# PayloadBay.net
KiCad netlist of a schematic drawn in EAGLE
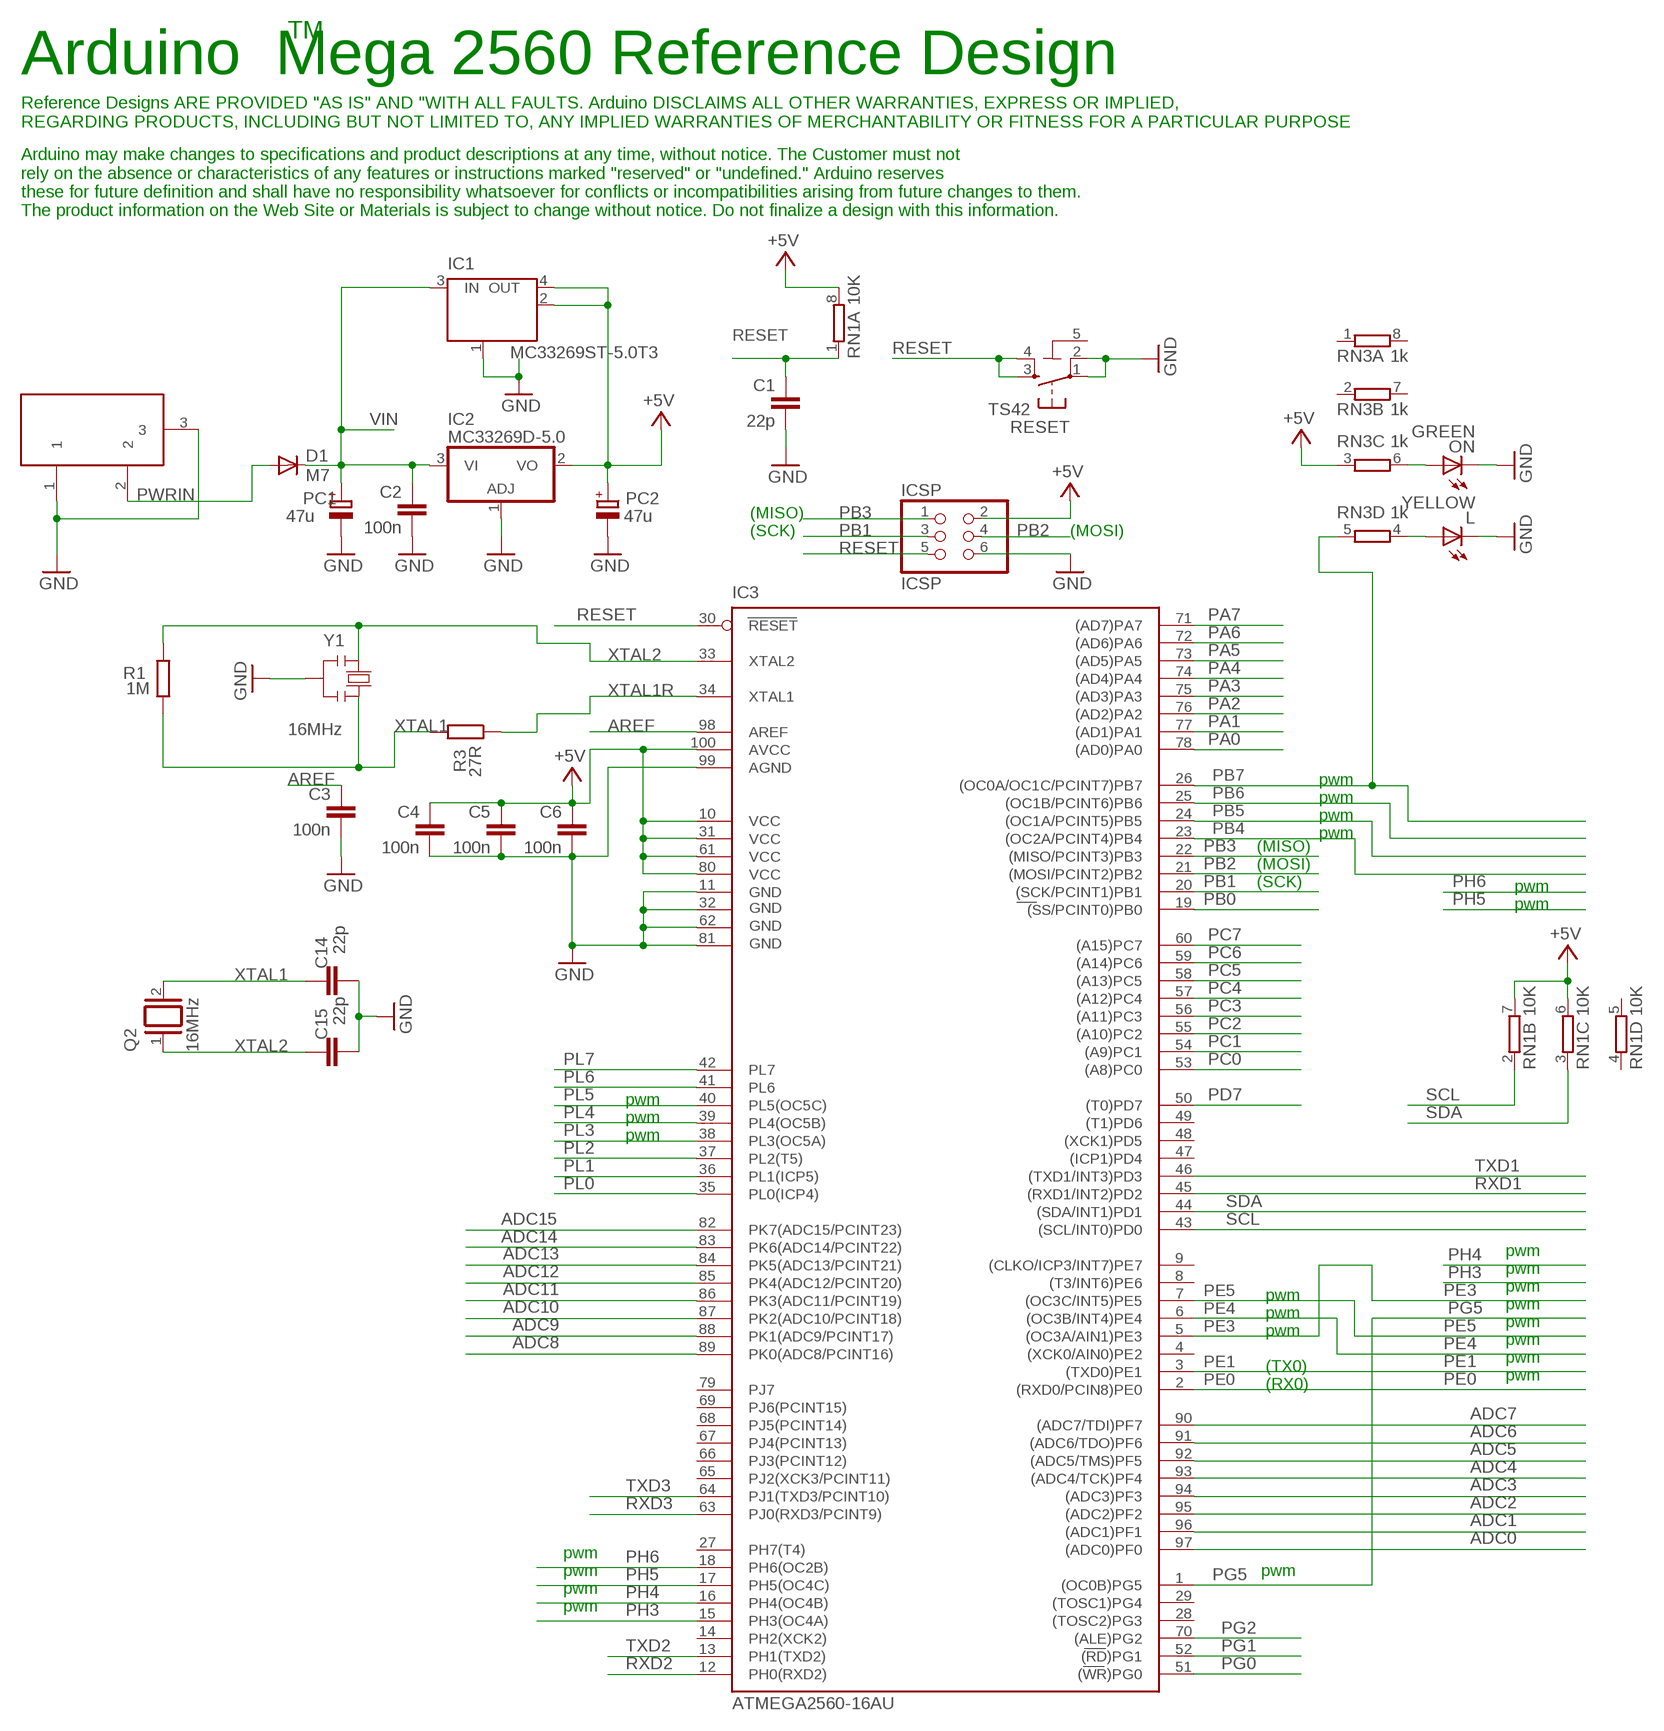
[diagram p0: schematic, sheet 1]

(export (version "E")
  (design (tool "Eeschema 10.0.6"))
  (components
    (comp (ref "C1")
      (value "22p")
      (footprint "eagle-import:C0603-ROUND")
      (libsource (lib "eagle-import") (part "C-EU0603-RND"))
    )
    (comp (ref "C2")
      (value "100n")
      (footprint "eagle-import:C0603-ROUND")
      (libsource (lib "eagle-import") (part "C-EU0603-RND"))
    )
    (comp (ref "C3")
      (value "100n")
      (footprint "eagle-import:C0603-ROUND")
      (libsource (lib "eagle-import") (part "C-EU0603-RND"))
    )
    (comp (ref "C4")
      (value "100n")
      (footprint "eagle-import:C0603-ROUND")
      (libsource (lib "eagle-import") (part "C-EU0603-RND"))
    )
    (comp (ref "C5")
      (value "100n")
      (footprint "eagle-import:C0603-ROUND")
      (libsource (lib "eagle-import") (part "C-EU0603-RND"))
    )
    (comp (ref "C6")
      (value "100n")
      (footprint "eagle-import:C0603-ROUND")
      (libsource (lib "eagle-import") (part "C-EU0603-RND"))
    )
    (comp (ref "C14")
      (value "22p")
      (footprint "eagle-import:C0603-ROUND")
      (libsource (lib "eagle-import") (part "C-EU0603-RND"))
    )
    (comp (ref "C15")
      (value "22p")
      (footprint "eagle-import:C0603-ROUND")
      (libsource (lib "eagle-import") (part "C-EU0603-RND"))
    )
    (comp (ref "D1")
      (value "M7")
      (footprint "eagle-import:SMB")
      (libsource (lib "eagle-import") (part "DIODE-SMB"))
    )
    (comp (ref "IC1")
      (value "MC33269ST-5.0T3")
      (footprint "eagle-import:SOT223")
      (libsource (lib "eagle-import") (part "MC33269ST-3.3T3"))
    )
    (comp (ref "IC2")
      (value "MC33269D-5.0")
      (footprint "eagle-import:DPACK")
      (libsource (lib "eagle-import") (part "MC33269?D-5.0"))
    )
    (comp (ref "IC3")
      (value "ATMEGA2560-16AU")
      (footprint "eagle-import:TQFP100")
      (libsource (lib "eagle-import") (part "ATMEGAAU1280-16"))
    )
    (comp (ref "ICSP")
      (value "ICSP")
      (footprint "eagle-import:2X03")
      (libsource (lib "eagle-import") (part "PINHD-2X3"))
    )
    (comp (ref "L")
      (value "YELLOW")
      (footprint "eagle-import:CHIP-LED0805")
      (libsource (lib "eagle-import") (part "LEDCHIP-LED0805"))
    )
    (comp (ref "ON")
      (value "GREEN")
      (footprint "eagle-import:CHIP-LED0805")
      (libsource (lib "eagle-import") (part "LEDCHIP-LED0805"))
    )
    (comp (ref "PC1")
      (value "47u")
      (footprint "eagle-import:PANASONIC_D")
      (libsource (lib "eagle-import") (part "CPOL-EUD"))
    )
    (comp (ref "PC2")
      (value "47u")
      (footprint "eagle-import:PANASONIC_D")
      (libsource (lib "eagle-import") (part "CPOL-EUD"))
    )
    (comp (ref "Q2")
      (value "16MHz")
      (footprint "eagle-import:QS")
      (libsource (lib "eagle-import") (part "XTAL/S"))
    )
    (comp (ref "R1")
      (value "1M")
      (footprint "eagle-import:R0603-ROUND")
      (libsource (lib "eagle-import") (part "R-EU_R0603"))
    )
    (comp (ref "R3")
      (value "27R")
      (footprint "eagle-import:R0603-ROUND")
      (libsource (lib "eagle-import") (part "R-EU_R0603"))
    )
    (comp (ref "RESET")
      (value "TS42")
      (footprint "eagle-import:TS42")
      (libsource (lib "eagle-import") (part "TS42"))
    )
    (comp (ref "RN1")
      (value "10K")
      (footprint "eagle-import:CAT16")
      (libsource (lib "eagle-import") (part "4R-NCAT16"))
    )
    (comp (ref "RN3")
      (value "1k")
      (footprint "eagle-import:CAY16")
      (libsource (lib "eagle-import") (part "4R-NCAY16"))
    )
    (comp (ref "X1")
      (value "DC21MMX")
      (footprint "eagle-import:DC-21MM")
      (libsource (lib "eagle-import") (part "DC21MMX"))
    )
    (comp (ref "Y1")
      (value "16MHz")
      (footprint "eagle-import:RESONATOR")
      (libsource (lib "eagle-import") (part "RESONATORMU"))
    )
  )
  (nets
    (net (code "1") (name "+5V") (class "Default")
      (node (ref "C4") (pin "1") (pinfunction "1_1") (pintype "passive"))
      (node (ref "C5") (pin "1") (pinfunction "1_1") (pintype "passive"))
      (node (ref "C6") (pin "1") (pinfunction "1_1") (pintype "passive"))
      (node (ref "IC1") (pin "2") (pinfunction "OUT_2") (pintype "passive"))
      (node (ref "IC1") (pin "4") (pinfunction "OUT_4") (pintype "passive"))
      (node (ref "IC2") (pin "2") (pinfunction "VO_2") (pintype "passive"))
      (node (ref "IC3") (pin "10") (pinfunction "VCC_10") (pintype "power_in"))
      (node (ref "IC3") (pin "100") (pinfunction "AVCC_100") (pintype "power_in"))
      (node (ref "IC3") (pin "31") (pinfunction "VCC1_31") (pintype "power_in"))
      (node (ref "IC3") (pin "61") (pinfunction "VCC2_61") (pintype "power_in"))
      (node (ref "IC3") (pin "80") (pinfunction "VCC3_80") (pintype "power_in"))
      (node (ref "ICSP") (pin "2") (pinfunction "2_2") (pintype "passive"))
      (node (ref "PC2") (pin "+") (pinfunction "+_+") (pintype "passive"))
      (node (ref "RN1") (pin "6") (pinfunction "2_6") (pintype "passive"))
      (node (ref "RN1") (pin "7") (pinfunction "2_7") (pintype "passive"))
      (node (ref "RN1") (pin "8") (pinfunction "2_8") (pintype "passive"))
      (node (ref "RN3") (pin "3") (pinfunction "1_3") (pintype "passive"))
    )
    (net (code "2") (name "/5-GND") (class "Default")
      (node (ref "RESET") (pin "5") (pinfunction "5-GND_5") (pintype "power_in"))
    )
    (net (code "3") (name "/ADC0") (class "Default")
      (node (ref "IC3") (pin "97") (pinfunction "(ADC0)PF0_97") (pintype "bidirectional"))
    )
    (net (code "4") (name "/ADC1") (class "Default")
      (node (ref "IC3") (pin "96") (pinfunction "(ADC1)PF1_96") (pintype "bidirectional"))
    )
    (net (code "5") (name "/ADC2") (class "Default")
      (node (ref "IC3") (pin "95") (pinfunction "(ADC2)PF2_95") (pintype "bidirectional"))
    )
    (net (code "6") (name "/ADC3") (class "Default")
      (node (ref "IC3") (pin "94") (pinfunction "(ADC3)PF3_94") (pintype "bidirectional"))
    )
    (net (code "7") (name "/ADC4") (class "Default")
      (node (ref "IC3") (pin "93") (pinfunction "(ADC4/TCK)PF4_93") (pintype "bidirectional"))
    )
    (net (code "8") (name "/ADC5") (class "Default")
      (node (ref "IC3") (pin "92") (pinfunction "(ADC5/TMS)PF5_92") (pintype "bidirectional"))
    )
    (net (code "9") (name "/ADC6") (class "Default")
      (node (ref "IC3") (pin "91") (pinfunction "(ADC6/TDO)PF6_91") (pintype "bidirectional"))
    )
    (net (code "10") (name "/ADC7") (class "Default")
      (node (ref "IC3") (pin "90") (pinfunction "(ADC7/TDI)PF7_90") (pintype "bidirectional"))
    )
    (net (code "11") (name "/ADC8") (class "Default")
      (node (ref "IC3") (pin "89") (pinfunction "PK0(ADC8/PCINT16)_89") (pintype "bidirectional"))
    )
    (net (code "12") (name "/ADC9") (class "Default")
      (node (ref "IC3") (pin "88") (pinfunction "PK1(ADC9/PCINT17)_88") (pintype "bidirectional"))
    )
    (net (code "13") (name "/ADC10") (class "Default")
      (node (ref "IC3") (pin "87") (pinfunction "PK2(ADC10/PCINT18)_87") (pintype "bidirectional"))
    )
    (net (code "14") (name "/ADC11") (class "Default")
      (node (ref "IC3") (pin "86") (pinfunction "PK3(ADC11/PCINT19)_86") (pintype "bidirectional"))
    )
    (net (code "15") (name "/ADC12") (class "Default")
      (node (ref "IC3") (pin "85") (pinfunction "PK4(ADC12/PCINT20)_85") (pintype "bidirectional"))
    )
    (net (code "16") (name "/ADC13") (class "Default")
      (node (ref "IC3") (pin "84") (pinfunction "PK5(ADC13/PCINT21)_84") (pintype "bidirectional"))
    )
    (net (code "17") (name "/ADC14") (class "Default")
      (node (ref "IC3") (pin "83") (pinfunction "PK6(ADC14/PCINT22)_83") (pintype "bidirectional"))
    )
    (net (code "18") (name "/ADC15") (class "Default")
      (node (ref "IC3") (pin "82") (pinfunction "PK7(ADC15/PCINT23)_82") (pintype "bidirectional"))
    )
    (net (code "19") (name "/AREF") (class "Default")
      (node (ref "C3") (pin "1") (pinfunction "1_1") (pintype "passive"))
      (node (ref "IC3") (pin "98") (pinfunction "AREF_98") (pintype "bidirectional"))
    )
    (net (code "20") (name "/PA0") (class "Default")
      (node (ref "IC3") (pin "78") (pinfunction "(AD0)PA0_78") (pintype "bidirectional"))
    )
    (net (code "21") (name "/PA1") (class "Default")
      (node (ref "IC3") (pin "77") (pinfunction "(AD1)PA1_77") (pintype "bidirectional"))
    )
    (net (code "22") (name "/PA2") (class "Default")
      (node (ref "IC3") (pin "76") (pinfunction "(AD2)PA2_76") (pintype "bidirectional"))
    )
    (net (code "23") (name "/PA3") (class "Default")
      (node (ref "IC3") (pin "75") (pinfunction "(AD3)PA3_75") (pintype "bidirectional"))
    )
    (net (code "24") (name "/PA4") (class "Default")
      (node (ref "IC3") (pin "74") (pinfunction "(AD4)PA4_74") (pintype "bidirectional"))
    )
    (net (code "25") (name "/PA5") (class "Default")
      (node (ref "IC3") (pin "73") (pinfunction "(AD5)PA5_73") (pintype "bidirectional"))
    )
    (net (code "26") (name "/PA6") (class "Default")
      (node (ref "IC3") (pin "72") (pinfunction "(AD6)PA6_72") (pintype "bidirectional"))
    )
    (net (code "27") (name "/PA7") (class "Default")
      (node (ref "IC3") (pin "71") (pinfunction "(AD7)PA7_71") (pintype "bidirectional"))
    )
    (net (code "28") (name "/PB0") (class "Default")
      (node (ref "IC3") (pin "19") (pinfunction "(SS/PCINT0)PB0_19") (pintype "bidirectional"))
    )
    (net (code "29") (name "/PB1") (class "Default")
      (node (ref "IC3") (pin "20") (pinfunction "(SCK/PCINT1)PB1_20") (pintype "bidirectional"))
      (node (ref "ICSP") (pin "3") (pinfunction "3_3") (pintype "passive"))
    )
    (net (code "30") (name "/PB2") (class "Default")
      (node (ref "IC3") (pin "21") (pinfunction "(MOSI/PCINT2)PB2_21") (pintype "bidirectional"))
      (node (ref "ICSP") (pin "4") (pinfunction "4_4") (pintype "passive"))
    )
    (net (code "31") (name "/PB3") (class "Default")
      (node (ref "IC3") (pin "22") (pinfunction "(MISO/PCINT3)PB3_22") (pintype "bidirectional"))
      (node (ref "ICSP") (pin "1") (pinfunction "1_1") (pintype "passive"))
    )
    (net (code "32") (name "/PB4") (class "Default")
      (node (ref "IC3") (pin "23") (pinfunction "(OC2A/PCINT4)PB4_23") (pintype "bidirectional"))
    )
    (net (code "33") (name "/PB5") (class "Default")
      (node (ref "IC3") (pin "24") (pinfunction "(OC1A/PCINT5)PB5_24") (pintype "bidirectional"))
    )
    (net (code "34") (name "/PB6") (class "Default")
      (node (ref "IC3") (pin "25") (pinfunction "(OC1B/PCINT6)PB6_25") (pintype "bidirectional"))
    )
    (net (code "35") (name "/PB7") (class "Default")
      (node (ref "IC3") (pin "26") (pinfunction "(OC0A/OC1C/PCINT7)PB7_26") (pintype "bidirectional"))
      (node (ref "RN3") (pin "5") (pinfunction "2_5") (pintype "passive"))
    )
    (net (code "36") (name "/PC0") (class "Default")
      (node (ref "IC3") (pin "53") (pinfunction "(A8)PC0_53") (pintype "bidirectional"))
    )
    (net (code "37") (name "/PC1") (class "Default")
      (node (ref "IC3") (pin "54") (pinfunction "(A9)PC1_54") (pintype "bidirectional"))
    )
    (net (code "38") (name "/PC2") (class "Default")
      (node (ref "IC3") (pin "55") (pinfunction "(A10)PC2_55") (pintype "bidirectional"))
    )
    (net (code "39") (name "/PC3") (class "Default")
      (node (ref "IC3") (pin "56") (pinfunction "(A11)PC3_56") (pintype "bidirectional"))
    )
    (net (code "40") (name "/PC4") (class "Default")
      (node (ref "IC3") (pin "57") (pinfunction "(A12)PC4_57") (pintype "bidirectional"))
    )
    (net (code "41") (name "/PC5") (class "Default")
      (node (ref "IC3") (pin "58") (pinfunction "(A13)PC5_58") (pintype "bidirectional"))
    )
    (net (code "42") (name "/PC6") (class "Default")
      (node (ref "IC3") (pin "59") (pinfunction "(A14)PC6_59") (pintype "bidirectional"))
    )
    (net (code "43") (name "/PC7") (class "Default")
      (node (ref "IC3") (pin "60") (pinfunction "(A15)PC7_60") (pintype "bidirectional"))
    )
    (net (code "44") (name "/PD7") (class "Default")
      (node (ref "IC3") (pin "50") (pinfunction "(T0)PD7_50") (pintype "bidirectional"))
    )
    (net (code "45") (name "/PE0") (class "Default")
      (node (ref "IC3") (pin "2") (pinfunction "(RXD0/PCIN8)PE0_2") (pintype "bidirectional"))
    )
    (net (code "46") (name "/PE1") (class "Default")
      (node (ref "IC3") (pin "3") (pinfunction "(TXD0)PE1_3") (pintype "bidirectional"))
    )
    (net (code "47") (name "/PE3") (class "Default")
      (node (ref "IC3") (pin "5") (pinfunction "(OC3A/AIN1)PE3_5") (pintype "bidirectional"))
    )
    (net (code "48") (name "/PE4") (class "Default")
      (node (ref "IC3") (pin "6") (pinfunction "(OC3B/INT4)PE4_6") (pintype "bidirectional"))
    )
    (net (code "49") (name "/PE5") (class "Default")
      (node (ref "IC3") (pin "7") (pinfunction "(OC3C/INT5)PE5_7") (pintype "bidirectional"))
    )
    (net (code "50") (name "/PG0") (class "Default")
      (node (ref "IC3") (pin "51") (pinfunction "(WR)PG0_51") (pintype "bidirectional"))
    )
    (net (code "51") (name "/PG1") (class "Default")
      (node (ref "IC3") (pin "52") (pinfunction "(RD)PG1_52") (pintype "bidirectional"))
    )
    (net (code "52") (name "/PG2") (class "Default")
      (node (ref "IC3") (pin "70") (pinfunction "(ALE)PG2_70") (pintype "bidirectional"))
    )
    (net (code "53") (name "/PG5") (class "Default")
      (node (ref "IC3") (pin "1") (pinfunction "(OC0B)PG5_1") (pintype "bidirectional"))
    )
    (net (code "54") (name "/PH3") (class "Default")
      (node (ref "IC3") (pin "15") (pinfunction "PH3(OC4A)_15") (pintype "bidirectional"))
    )
    (net (code "55") (name "/PH4") (class "Default")
      (node (ref "IC3") (pin "16") (pinfunction "PH4(OC4B)_16") (pintype "bidirectional"))
    )
    (net (code "56") (name "/PH5") (class "Default")
      (node (ref "IC3") (pin "17") (pinfunction "PH5(OC4C)_17") (pintype "bidirectional"))
    )
    (net (code "57") (name "/PH6") (class "Default")
      (node (ref "IC3") (pin "18") (pinfunction "PH6(OC2B)_18") (pintype "bidirectional"))
    )
    (net (code "58") (name "/PL0") (class "Default")
      (node (ref "IC3") (pin "35") (pinfunction "PL0(ICP4)_35") (pintype "bidirectional"))
    )
    (net (code "59") (name "/PL1") (class "Default")
      (node (ref "IC3") (pin "36") (pinfunction "PL1(ICP5)_36") (pintype "bidirectional"))
    )
    (net (code "60") (name "/PL2") (class "Default")
      (node (ref "IC3") (pin "37") (pinfunction "PL2(T5)_37") (pintype "bidirectional"))
    )
    (net (code "61") (name "/PL3") (class "Default")
      (node (ref "IC3") (pin "38") (pinfunction "PL3(OC5A)_38") (pintype "bidirectional"))
    )
    (net (code "62") (name "/PL4") (class "Default")
      (node (ref "IC3") (pin "39") (pinfunction "PL4(OC5B)_39") (pintype "bidirectional"))
    )
    (net (code "63") (name "/PL5") (class "Default")
      (node (ref "IC3") (pin "40") (pinfunction "PL5(OC5C)_40") (pintype "bidirectional"))
    )
    (net (code "64") (name "/PL6") (class "Default")
      (node (ref "IC3") (pin "41") (pinfunction "PL6_41") (pintype "bidirectional"))
    )
    (net (code "65") (name "/PL7") (class "Default")
      (node (ref "IC3") (pin "42") (pinfunction "PL7_42") (pintype "bidirectional"))
    )
    (net (code "66") (name "/PWRIN") (class "Default")
      (node (ref "D1") (pin "A") (pinfunction "A_A") (pintype "passive"))
      (node (ref "X1") (pin "2") (pinfunction "2_2") (pintype "power_in"))
    )
    (net (code "67") (name "/RESET") (class "Default")
      (node (ref "C1") (pin "1") (pinfunction "1_1") (pintype "passive"))
      (node (ref "IC3") (pin "30") (pinfunction "RESET_30") (pintype "input"))
      (node (ref "ICSP") (pin "5") (pinfunction "5_5") (pintype "passive"))
      (node (ref "RESET") (pin "3") (pinfunction "3_3") (pintype "passive"))
      (node (ref "RESET") (pin "4") (pinfunction "4_4") (pintype "passive"))
      (node (ref "RN1") (pin "1") (pinfunction "1_1") (pintype "passive"))
    )
    (net (code "68") (name "/RXD1") (class "Default")
      (node (ref "IC3") (pin "45") (pinfunction "(RXD1/INT2)PD2_45") (pintype "bidirectional"))
    )
    (net (code "69") (name "/RXD2") (class "Default")
      (node (ref "IC3") (pin "12") (pinfunction "PH0(RXD2)_12") (pintype "bidirectional"))
    )
    (net (code "70") (name "/RXD3") (class "Default")
      (node (ref "IC3") (pin "63") (pinfunction "PJ0(RXD3/PCINT9)_63") (pintype "bidirectional"))
    )
    (net (code "71") (name "/SCL") (class "Default")
      (node (ref "IC3") (pin "43") (pinfunction "(SCL/INT0)PD0_43") (pintype "bidirectional"))
      (node (ref "RN1") (pin "2") (pinfunction "1_2") (pintype "passive"))
    )
    (net (code "72") (name "/SDA") (class "Default")
      (node (ref "IC3") (pin "44") (pinfunction "(SDA/INT1)PD1_44") (pintype "bidirectional"))
      (node (ref "RN1") (pin "3") (pinfunction "1_3") (pintype "passive"))
    )
    (net (code "73") (name "/TXD1") (class "Default")
      (node (ref "IC3") (pin "46") (pinfunction "(TXD1/INT3)PD3_46") (pintype "bidirectional"))
    )
    (net (code "74") (name "/TXD2") (class "Default")
      (node (ref "IC3") (pin "13") (pinfunction "PH1(TXD2)_13") (pintype "bidirectional"))
    )
    (net (code "75") (name "/TXD3") (class "Default")
      (node (ref "IC3") (pin "64") (pinfunction "PJ1(TXD3/PCINT10)_64") (pintype "bidirectional"))
    )
    (net (code "76") (name "/VIN") (class "Default")
      (node (ref "C2") (pin "1") (pinfunction "1_1") (pintype "passive"))
      (node (ref "D1") (pin "C") (pinfunction "C_C") (pintype "passive"))
      (node (ref "IC1") (pin "3") (pinfunction "IN_3") (pintype "input"))
      (node (ref "IC2") (pin "3") (pinfunction "VI_3") (pintype "input"))
      (node (ref "PC1") (pin "+") (pinfunction "+_+") (pintype "passive"))
    )
    (net (code "77") (name "/XTAL1") (class "Default")
      (node (ref "C14") (pin "2") (pinfunction "2_2") (pintype "passive"))
      (node (ref "Q2") (pin "2") (pinfunction "2_2") (pintype "passive"))
      (node (ref "R1") (pin "1") (pinfunction "1_1") (pintype "passive"))
      (node (ref "R3") (pin "2") (pinfunction "2_2") (pintype "passive"))
      (node (ref "Y1") (pin "3") (pinfunction "3_3") (pintype "passive"))
    )
    (net (code "78") (name "/XTAL1R") (class "Default")
      (node (ref "IC3") (pin "34") (pinfunction "XTAL1_34") (pintype "input"))
      (node (ref "R3") (pin "1") (pinfunction "1_1") (pintype "passive"))
    )
    (net (code "79") (name "/XTAL2") (class "Default")
      (node (ref "C15") (pin "2") (pinfunction "2_2") (pintype "passive"))
      (node (ref "IC3") (pin "33") (pinfunction "XTAL2_33") (pintype "output"))
      (node (ref "Q2") (pin "1") (pinfunction "1_1") (pintype "passive"))
      (node (ref "R1") (pin "2") (pinfunction "2_2") (pintype "passive"))
      (node (ref "Y1") (pin "1") (pinfunction "1_1") (pintype "passive"))
    )
    (net (code "80") (name "GND") (class "Default")
      (node (ref "C1") (pin "2") (pinfunction "2_2") (pintype "passive"))
      (node (ref "C14") (pin "1") (pinfunction "1_1") (pintype "passive"))
      (node (ref "C15") (pin "1") (pinfunction "1_1") (pintype "passive"))
      (node (ref "C2") (pin "2") (pinfunction "2_2") (pintype "passive"))
      (node (ref "C3") (pin "2") (pinfunction "2_2") (pintype "passive"))
      (node (ref "C4") (pin "2") (pinfunction "2_2") (pintype "passive"))
      (node (ref "C5") (pin "2") (pinfunction "2_2") (pintype "passive"))
      (node (ref "C6") (pin "2") (pinfunction "2_2") (pintype "passive"))
      (node (ref "IC1") (pin "1") (pinfunction "GND/ADJ_1") (pintype "input"))
      (node (ref "IC2") (pin "1") (pinfunction "ADJ_1") (pintype "input"))
      (node (ref "IC3") (pin "11") (pinfunction "GND_11") (pintype "power_in"))
      (node (ref "IC3") (pin "32") (pinfunction "GND1_32") (pintype "power_in"))
      (node (ref "IC3") (pin "62") (pinfunction "GND2_62") (pintype "power_in"))
      (node (ref "IC3") (pin "81") (pinfunction "GND3_81") (pintype "power_in"))
      (node (ref "IC3") (pin "99") (pinfunction "AGND_99") (pintype "power_in"))
      (node (ref "ICSP") (pin "6") (pinfunction "6_6") (pintype "passive"))
      (node (ref "L") (pin "C") (pinfunction "C_C") (pintype "passive"))
      (node (ref "ON") (pin "C") (pinfunction "C_C") (pintype "passive"))
      (node (ref "PC1") (pin "-") (pinfunction "-_-") (pintype "passive"))
      (node (ref "PC2") (pin "-") (pinfunction "-_-") (pintype "passive"))
      (node (ref "RESET") (pin "1") (pinfunction "1_1") (pintype "passive"))
      (node (ref "RESET") (pin "2") (pinfunction "2_2") (pintype "passive"))
      (node (ref "X1") (pin "1") (pinfunction "1_1") (pintype "power_in"))
      (node (ref "X1") (pin "3") (pinfunction "3_3") (pintype "power_in"))
      (node (ref "Y1") (pin "2") (pinfunction "2_2") (pintype "passive"))
    )
    (net (code "81") (name "Net-(RN3C-2)") (class "Default")
      (node (ref "ON") (pin "A") (pinfunction "A_A") (pintype "passive"))
      (node (ref "RN3") (pin "6") (pinfunction "2_6") (pintype "passive"))
    )
    (net (code "82") (name "Net-(RN3D-1)") (class "Default")
      (node (ref "L") (pin "A") (pinfunction "A_A") (pintype "passive"))
      (node (ref "RN3") (pin "4") (pinfunction "1_4") (pintype "passive"))
    )
    (net (code "83") (name "unconnected-(IC3-(CLKO{slash}ICP3{slash}INT7)PE7-Pad9)") (class "Default")
      (node (ref "IC3") (pin "9") (pinfunction "(CLKO/ICP3/INT7)PE7_9") (pintype "bidirectional"))
    )
    (net (code "84") (name "unconnected-(IC3-(ICP1)PD4-Pad47)") (class "Default")
      (node (ref "IC3") (pin "47") (pinfunction "(ICP1)PD4_47") (pintype "bidirectional"))
    )
    (net (code "85") (name "unconnected-(IC3-(T1)PD6-Pad49)") (class "Default")
      (node (ref "IC3") (pin "49") (pinfunction "(T1)PD6_49") (pintype "bidirectional"))
    )
    (net (code "86") (name "unconnected-(IC3-(T3{slash}INT6)PE6-Pad8)") (class "Default")
      (node (ref "IC3") (pin "8") (pinfunction "(T3/INT6)PE6_8") (pintype "bidirectional"))
    )
    (net (code "87") (name "unconnected-(IC3-(TOSC1)PG4-Pad29)") (class "Default")
      (node (ref "IC3") (pin "29") (pinfunction "(TOSC1)PG4_29") (pintype "bidirectional"))
    )
    (net (code "88") (name "unconnected-(IC3-(TOSC2)PG3-Pad28)") (class "Default")
      (node (ref "IC3") (pin "28") (pinfunction "(TOSC2)PG3_28") (pintype "bidirectional"))
    )
    (net (code "89") (name "unconnected-(IC3-(XCK0{slash}AIN0)PE2-Pad4)") (class "Default")
      (node (ref "IC3") (pin "4") (pinfunction "(XCK0/AIN0)PE2_4") (pintype "bidirectional"))
    )
    (net (code "90") (name "unconnected-(IC3-(XCK1)PD5-Pad48)") (class "Default")
      (node (ref "IC3") (pin "48") (pinfunction "(XCK1)PD5_48") (pintype "bidirectional"))
    )
    (net (code "91") (name "unconnected-(IC3-PH2(XCK2)-Pad14)") (class "Default")
      (node (ref "IC3") (pin "14") (pinfunction "PH2(XCK2)_14") (pintype "bidirectional"))
    )
    (net (code "92") (name "unconnected-(IC3-PH7(T4)-Pad27)") (class "Default")
      (node (ref "IC3") (pin "27") (pinfunction "PH7(T4)_27") (pintype "bidirectional"))
    )
    (net (code "93") (name "unconnected-(IC3-PJ2(XCK3{slash}PCINT11)-Pad65)") (class "Default")
      (node (ref "IC3") (pin "65") (pinfunction "PJ2(XCK3/PCINT11)_65") (pintype "bidirectional"))
    )
    (net (code "94") (name "unconnected-(IC3-PJ3(PCINT12)-Pad66)") (class "Default")
      (node (ref "IC3") (pin "66") (pinfunction "PJ3(PCINT12)_66") (pintype "bidirectional"))
    )
    (net (code "95") (name "unconnected-(IC3-PJ4(PCINT13)-Pad67)") (class "Default")
      (node (ref "IC3") (pin "67") (pinfunction "PJ4(PCINT13)_67") (pintype "bidirectional"))
    )
    (net (code "96") (name "unconnected-(IC3-PJ5(PCINT14)-Pad68)") (class "Default")
      (node (ref "IC3") (pin "68") (pinfunction "PJ5(PCINT14)_68") (pintype "bidirectional"))
    )
    (net (code "97") (name "unconnected-(IC3-PJ6(PCINT15)-Pad69)") (class "Default")
      (node (ref "IC3") (pin "69") (pinfunction "PJ6(PCINT15)_69") (pintype "bidirectional"))
    )
    (net (code "98") (name "unconnected-(IC3-PJ7-Pad79)") (class "Default")
      (node (ref "IC3") (pin "79") (pinfunction "PJ7_79") (pintype "bidirectional"))
    )
    (net (code "99") (name "unconnected-(RN1D-1-Pad4)") (class "Default")
      (node (ref "RN1") (pin "4") (pinfunction "1_4") (pintype "passive"))
    )
    (net (code "100") (name "unconnected-(RN1D-2-Pad5)") (class "Default")
      (node (ref "RN1") (pin "5") (pinfunction "2_5") (pintype "passive"))
    )
    (net (code "101") (name "unconnected-(RN3-Pad1)") (class "Default")
      (node (ref "RN3") (pin "1") (pinfunction "1_1") (pintype "passive"))
    )
    (net (code "102") (name "unconnected-(RN3A-2-Pad8)") (class "Default")
      (node (ref "RN3") (pin "8") (pinfunction "2_8") (pintype "passive"))
    )
    (net (code "103") (name "unconnected-(RN3B-1-Pad2)") (class "Default")
      (node (ref "RN3") (pin "2") (pinfunction "1_2") (pintype "passive"))
    )
    (net (code "104") (name "unconnected-(RN3B-2-Pad7)") (class "Default")
      (node (ref "RN3") (pin "7") (pinfunction "2_7") (pintype "passive"))
    )
  )
)
